# m20048_GPS.net
KiCad netlist of a schematic drawn in Altium Designer
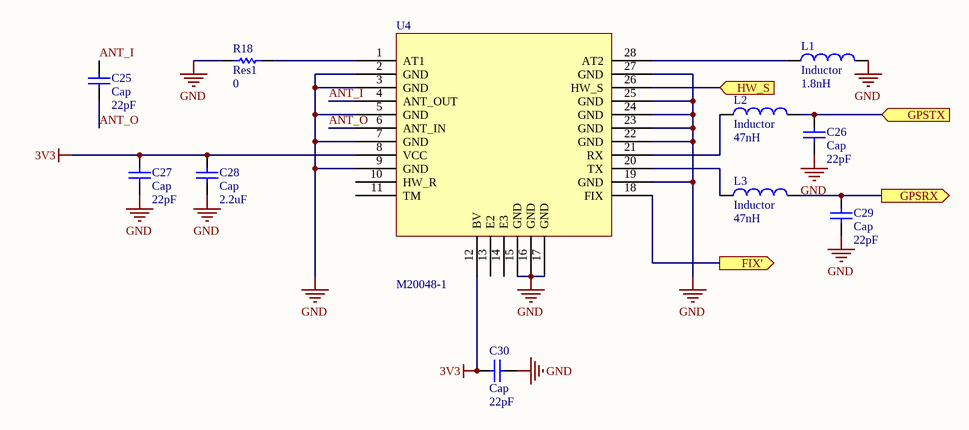
[diagram p0: m20048 GPS.SchDoc]

(export (version "E")
  (design (tool "Eeschema 10.0.6"))
  (components
    (comp (ref "C25")
      (value "Cap")
      (footprint "0402-A")
      (description "Capacitor")
      (fields (field (name "ALTIUM_VALUE") "22pF") (field (name "PUBLISHER") "Altium Limited"))
      (libsource (lib "Miscellaneous Devices") (part "Cap"))
    )
    (comp (ref "C26")
      (value "Cap")
      (footprint "0402-A")
      (description "Capacitor")
      (fields (field (name "ALTIUM_VALUE") "22pF") (field (name "PUBLISHER") "Altium Limited"))
      (libsource (lib "Miscellaneous Devices") (part "Cap"))
    )
    (comp (ref "C27")
      (value "Cap")
      (footprint "0402-A")
      (description "Capacitor")
      (fields (field (name "ALTIUM_VALUE") "22pF") (field (name "PUBLISHER") "Altium Limited"))
      (libsource (lib "Miscellaneous Devices") (part "Cap"))
    )
    (comp (ref "C28")
      (value "Cap")
      (footprint "0402-A")
      (description "Capacitor")
      (fields (field (name "ALTIUM_VALUE") "2.2uF") (field (name "PUBLISHER") "Altium Limited"))
      (libsource (lib "Miscellaneous Devices") (part "Cap"))
    )
    (comp (ref "C29")
      (value "Cap")
      (footprint "0402-A")
      (description "Capacitor")
      (fields (field (name "ALTIUM_VALUE") "22pF") (field (name "PUBLISHER") "Altium Limited"))
      (libsource (lib "Miscellaneous Devices") (part "Cap"))
    )
    (comp (ref "C30")
      (value "Cap")
      (footprint "0402-A")
      (description "Capacitor")
      (fields (field (name "ALTIUM_VALUE") "22pF") (field (name "PUBLISHER") "Altium Limited"))
      (libsource (lib "Miscellaneous Devices") (part "Cap"))
    )
    (comp (ref "L1")
      (value "Inductor")
      (footprint "0402-A")
      (fields (field (name "ALTIUM_VALUE") "1.8nH") (field (name "PUBLISHER") "Altium Limited"))
      (libsource (lib "Miscellaneous Devices") (part "Inductor"))
    )
    (comp (ref "L2")
      (value "Inductor")
      (footprint "0402-A")
      (fields (field (name "ALTIUM_VALUE") "47nH") (field (name "PUBLISHER") "Altium Limited"))
      (libsource (lib "Miscellaneous Devices") (part "Inductor"))
    )
    (comp (ref "L3")
      (value "Inductor")
      (footprint "0402-A")
      (fields (field (name "ALTIUM_VALUE") "47nH") (field (name "PUBLISHER") "Altium Limited"))
      (libsource (lib "Miscellaneous Devices") (part "Inductor"))
    )
    (comp (ref "R18")
      (value "Res1")
      (footprint "0402-A")
      (description "Resistor")
      (fields (field (name "ALTIUM_VALUE") "0") (field (name "PUBLISHER") "Altium Limited"))
      (libsource (lib "Miscellaneous Devices") (part "Res1"))
    )
    (comp (ref "U4") (value "M20048-1") (footprint "M20048-1") (libsource (lib "m20048") (part "M20048-1")))
  )
  (nets
    (net (code "1") (name "/ANT_I") (class "Default")
      (node (ref "C25") (pin "2") (pinfunction "2_2") (pintype "passive"))
      (node (ref "U4") (pin "4") (pinfunction "ANT_OUT_4") (pintype "passive"))
    )
    (net (code "2") (name "/ANT_O") (class "Default")
      (node (ref "C25") (pin "1") (pinfunction "1_1") (pintype "passive"))
      (node (ref "U4") (pin "6") (pinfunction "ANT_IN_6") (pintype "passive"))
    )
    (net (code "3") (name "/FIX'") (class "Default")
      (node (ref "U4") (pin "18") (pinfunction "FIX_18") (pintype "passive"))
    )
    (net (code "4") (name "/GPSRX") (class "Default")
      (node (ref "C29") (pin "2") (pinfunction "2_2") (pintype "passive"))
      (node (ref "L3") (pin "2") (pinfunction "2_2") (pintype "passive"))
    )
    (net (code "5") (name "/GPSTX") (class "Default")
      (node (ref "C26") (pin "2") (pinfunction "2_2") (pintype "passive"))
      (node (ref "L2") (pin "2") (pinfunction "2_2") (pintype "passive"))
    )
    (net (code "6") (name "/HW_S") (class "Default")
      (node (ref "U4") (pin "26") (pinfunction "HW_S_26") (pintype "passive"))
    )
    (net (code "7") (name "3V3") (class "Default")
      (node (ref "C27") (pin "2") (pinfunction "2_2") (pintype "passive"))
      (node (ref "C28") (pin "2") (pinfunction "2_2") (pintype "passive"))
      (node (ref "C30") (pin "2") (pinfunction "2_2") (pintype "passive"))
      (node (ref "U4") (pin "12") (pinfunction "BV_12") (pintype "passive"))
      (node (ref "U4") (pin "8") (pinfunction "VCC_8") (pintype "passive"))
    )
    (net (code "8") (name "GND") (class "Default")
      (node (ref "C26") (pin "1") (pinfunction "1_1") (pintype "passive"))
      (node (ref "C27") (pin "1") (pinfunction "1_1") (pintype "passive"))
      (node (ref "C28") (pin "1") (pinfunction "1_1") (pintype "passive"))
      (node (ref "C29") (pin "1") (pinfunction "1_1") (pintype "passive"))
      (node (ref "C30") (pin "1") (pinfunction "1_1") (pintype "passive"))
      (node (ref "L1") (pin "2") (pinfunction "2_2") (pintype "passive"))
      (node (ref "R18") (pin "1") (pinfunction "1_1") (pintype "passive"))
      (node (ref "U4") (pin "15") (pinfunction "GND_15") (pintype "passive"))
      (node (ref "U4") (pin "16") (pinfunction "GND_16") (pintype "passive"))
      (node (ref "U4") (pin "17") (pinfunction "GND_17") (pintype "passive"))
      (node (ref "U4") (pin "19") (pinfunction "GND_19") (pintype "passive"))
      (node (ref "U4") (pin "2") (pinfunction "GND_2") (pintype "passive"))
      (node (ref "U4") (pin "22") (pinfunction "GND_22") (pintype "passive"))
      (node (ref "U4") (pin "23") (pinfunction "GND_23") (pintype "passive"))
      (node (ref "U4") (pin "24") (pinfunction "GND_24") (pintype "passive"))
      (node (ref "U4") (pin "25") (pinfunction "GND_25") (pintype "passive"))
      (node (ref "U4") (pin "27") (pinfunction "GND_27") (pintype "passive"))
      (node (ref "U4") (pin "3") (pinfunction "GND_3") (pintype "passive"))
      (node (ref "U4") (pin "5") (pinfunction "GND_5") (pintype "passive"))
      (node (ref "U4") (pin "7") (pinfunction "GND_7") (pintype "passive"))
      (node (ref "U4") (pin "9") (pinfunction "GND_9") (pintype "passive"))
    )
    (net (code "9") (name "Net-(U4-AT1)") (class "Default")
      (node (ref "R18") (pin "2") (pinfunction "2_2") (pintype "passive"))
      (node (ref "U4") (pin "1") (pinfunction "AT1_1") (pintype "passive"))
    )
    (net (code "10") (name "Net-(U4-AT2)") (class "Default")
      (node (ref "L1") (pin "1") (pinfunction "1_1") (pintype "passive"))
      (node (ref "U4") (pin "28") (pinfunction "AT2_28") (pintype "passive"))
    )
    (net (code "11") (name "Net-(U4-RX)") (class "Default")
      (node (ref "L2") (pin "1") (pinfunction "1_1") (pintype "passive"))
      (node (ref "U4") (pin "21") (pinfunction "RX_21") (pintype "passive"))
    )
    (net (code "12") (name "Net-(U4-TX)") (class "Default")
      (node (ref "L3") (pin "1") (pinfunction "1_1") (pintype "passive"))
      (node (ref "U4") (pin "20") (pinfunction "TX_20") (pintype "passive"))
    )
    (net (code "13") (name "unconnected-(U4-E2-Pad13)") (class "Default")
      (node (ref "U4") (pin "13") (pinfunction "E2_13") (pintype "passive"))
    )
    (net (code "14") (name "unconnected-(U4-E3-Pad14)") (class "Default")
      (node (ref "U4") (pin "14") (pinfunction "E3_14") (pintype "passive"))
    )
    (net (code "15") (name "unconnected-(U4-HW_R-Pad10)") (class "Default")
      (node (ref "U4") (pin "10") (pinfunction "HW_R_10") (pintype "passive"))
    )
    (net (code "16") (name "unconnected-(U4-TM-Pad11)") (class "Default")
      (node (ref "U4") (pin "11") (pinfunction "TM_11") (pintype "passive"))
    )
  )
)
